# zasilanie.net
KiCad netlist of a schematic drawn in Altium Designer
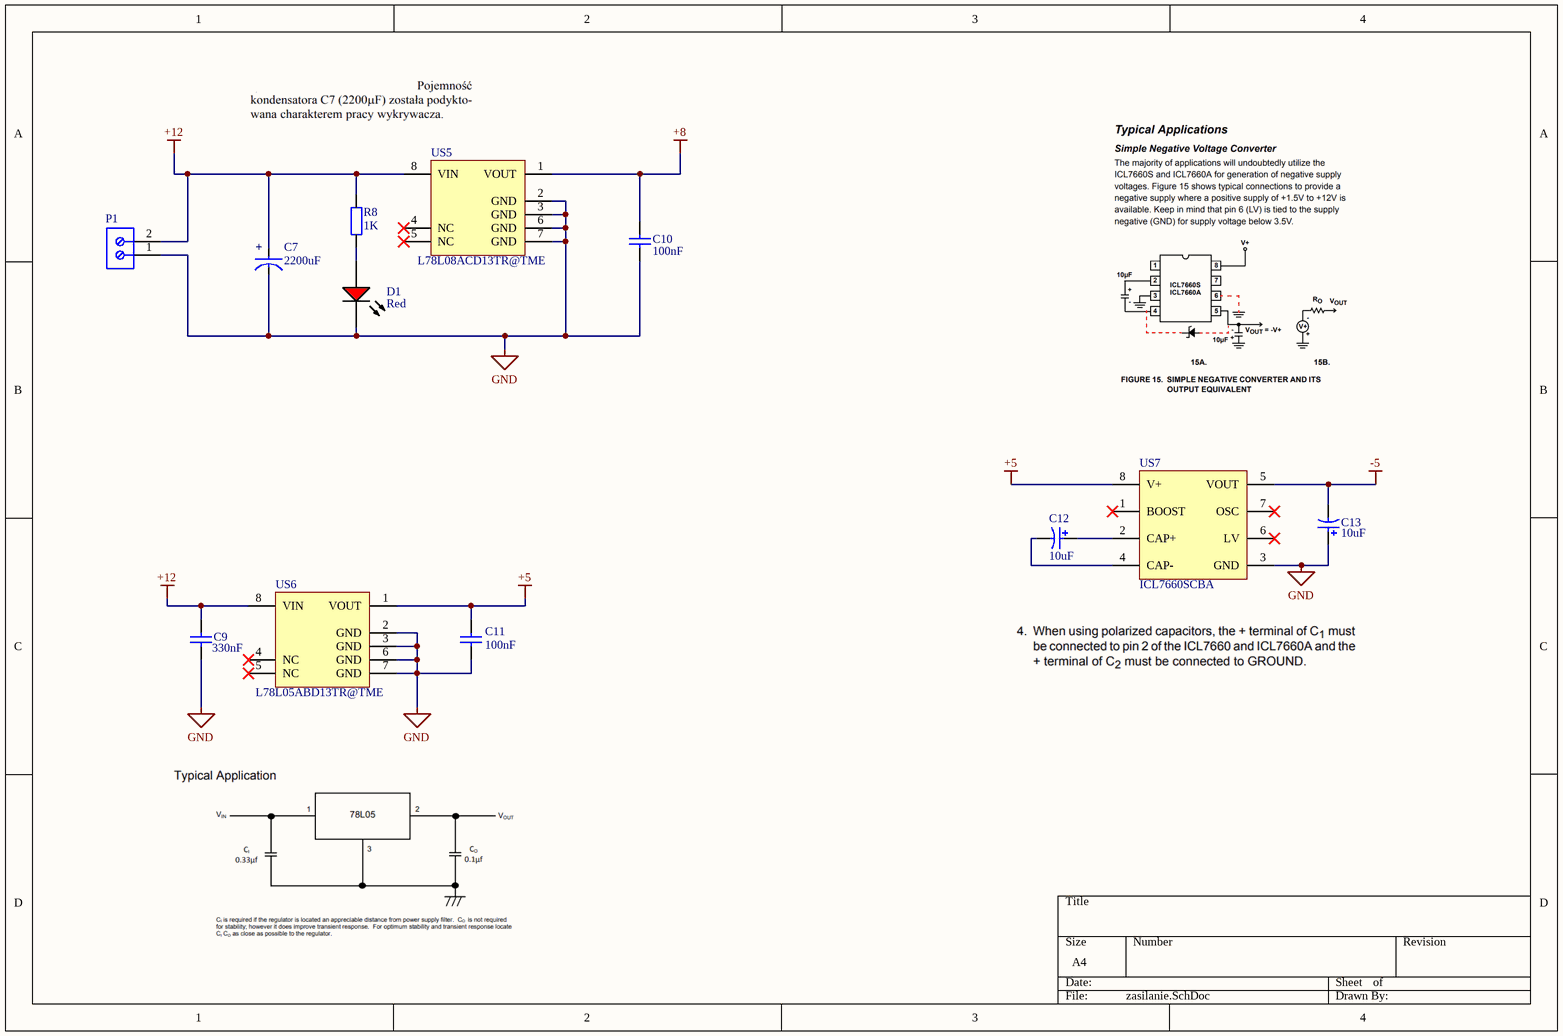
[diagram p0: zasilanie.SchDoc]

(export (version "E")
  (design (tool "Eeschema 10.0.6"))
  (components
    (comp (ref "C7")
      (value "Cap Electrolytic")
      (footprint "Capacitors_MT_Library:18 X 25mm Radial 7.5mm")
      (description "CAPACITOR ALUM 2200UF 20% 35V RADIAL")
      (fields (field (name "CAPACITANCE") "2200uF"))
      (libsource (lib "MT_Library") (part "Cap Electrolytic"))
    )
    (comp (ref "C9")
      (value "330nF")
      (footprint "CAPC1608X90X35ML15T15")
      (fields
        (field (name "PART NUMBER") "0603YD334KAT2A")
        (field (name "MANUFACTURER") "AVX Interconnect / Elco")
      )
      (libsource (lib "Altium Content Vault") (part "CAP"))
    )
    (comp (ref "C10")
      (value "CL10B104KA8NNNC@TME")
      (footprint "0603")
      (description "Capacitor")
      (fields (field (name "CAPACITANCE") "100nF"))
      (libsource (lib "MT_Library") (part "Cap"))
    )
    (comp (ref "C11")
      (value "CL10B104KA8NNNC@TME")
      (footprint "0603")
      (description "Capacitor")
      (fields (field (name "CAPACITANCE") "100nF"))
      (libsource (lib "MT_Library") (part "Cap"))
    )
    (comp (ref "C12")
      (value "EEEFK1H100P")
      (footprint "PNSC-FK-V-D_V")
      (fields (field (name "MANUFACTURER") "Panasonic") (field (name "CAPACITANCE") "10uF"))
      (libsource (lib "Altium Content Vault") (part "CAP-P-2"))
    )
    (comp (ref "C13")
      (value "EEEFK1H100P")
      (footprint "PNSC-FK-V-D_V")
      (fields (field (name "MANUFACTURER") "Panasonic") (field (name "CAPACITANCE") "10uF"))
      (libsource (lib "Altium Content Vault") (part "CAP-P-2"))
    )
    (comp (ref "D1")
      (value "TLMS1000-GS08")
      (footprint "VISH-TLMS1000_V")
      (description "Low Current LED, 40 mW, 1.8 V, -40 to 100 degC, 2-Pin SMD (0603), RoHS, Tape and Reel")
      (fields (field (name "LED COLOUR") "Red") (field (name "MANUFACTURER") "Vishay"))
      (libsource (lib "Altium Content Vault") (part "LED-RED-AK-2"))
    )
    (comp (ref "P1")
      (value "282836-2@TME")
      (footprint "TECO-282836-2_V")
      (description "Female Header, Pitch 5 mm, 1 x 2 Position, Height 10 mm, Tail Length 3.5 mm, Rohs, Bulk")
      (fields (field (name "VOLTAGE") "300V") (field (name "MANUFACTURER") "TE Connectivity"))
      (libsource (lib "Altium Content Vault") (part "CN-1P-F-TB2"))
    )
    (comp (ref "R8")
      (value "1K")
      (footprint "R1206")
      (description "Resistor")
      (fields (field (name "Comment") "1206S4J0102T5E@TME"))
      (libsource (lib "MT_Library") (part "Res"))
    )
    (comp (ref "US5")
      (value "L78L08ACD13TR@TME")
      (footprint "SO8_M")
      (description "Positive Voltage Regulator, 8V, 8-Pin SO, Tape and Reel")
      (libsource (lib "Altium Content Vault") (part "PM-REG-7805-IL8"))
    )
    (comp (ref "US6")
      (value "L78L05ABD13TR@TME")
      (footprint "SO8_N")
      (description "Positive Voltage Regulator, 5V, 8-Pin SO, Tape and Reel")
      (libsource (lib "Altium Content Vault") (part "PM-REG-7805-IL8"))
    )
    (comp (ref "US7")
      (value "ICL7660SCBA")
      (footprint "INTS-SOIC-8_V")
      (fields (field (name "MANUFACTURER") "Intersil"))
      (libsource (lib "Altium Content Vault") (part "INTS-ICL7660S-8"))
    )
  )
  (nets
    (net (code "1") (name "+5") (class "Default")
      (node (ref "C11") (pin "1") (pinfunction "1_1") (pintype "passive"))
      (node (ref "US6") (pin "1") (pinfunction "VOUT_1") (pintype "power_in"))
      (node (ref "US7") (pin "8") (pinfunction "V+_8") (pintype "power_in"))
    )
    (net (code "2") (name "+8") (class "Default")
      (node (ref "C10") (pin "1") (pinfunction "1_1") (pintype "passive"))
      (node (ref "US5") (pin "1") (pinfunction "VOUT_1") (pintype "power_in"))
    )
    (net (code "3") (name "+12") (class "Default")
      (node (ref "C7") (pin "2") (pinfunction "+_2") (pintype "passive"))
      (node (ref "C9") (pin "1") (pinfunction "1_1") (pintype "passive"))
      (node (ref "P1") (pin "2") (pinfunction "-_2") (pintype "power_in"))
      (node (ref "R8") (pin "2") (pinfunction "2_2") (pintype "passive"))
      (node (ref "US5") (pin "8") (pinfunction "VIN_8") (pintype "power_in"))
      (node (ref "US6") (pin "8") (pinfunction "VIN_8") (pintype "power_in"))
    )
    (net (code "4") (name "-5") (class "Default")
      (node (ref "C13") (pin "2") (pinfunction "2_2") (pintype "passive"))
      (node (ref "US7") (pin "5") (pinfunction "VOUT_5") (pintype "power_in"))
    )
    (net (code "5") (name "GND") (class "Default")
      (node (ref "C10") (pin "2") (pinfunction "2_2") (pintype "passive"))
      (node (ref "C11") (pin "2") (pinfunction "2_2") (pintype "passive"))
      (node (ref "C13") (pin "1") (pinfunction "1_1") (pintype "passive"))
      (node (ref "C7") (pin "1") (pinfunction "-_1") (pintype "passive"))
      (node (ref "C9") (pin "2") (pinfunction "2_2") (pintype "passive"))
      (node (ref "D1") (pin "2") (pinfunction "K_2") (pintype "passive"))
      (node (ref "P1") (pin "1") (pinfunction "+_1") (pintype "power_in"))
      (node (ref "US5") (pin "2") (pinfunction "GND_2") (pintype "power_in"))
      (node (ref "US5") (pin "3") (pinfunction "GND_3") (pintype "power_in"))
      (node (ref "US5") (pin "6") (pinfunction "GND_6") (pintype "power_in"))
      (node (ref "US5") (pin "7") (pinfunction "GND_7") (pintype "power_in"))
      (node (ref "US6") (pin "2") (pinfunction "GND_2") (pintype "power_in"))
      (node (ref "US6") (pin "3") (pinfunction "GND_3") (pintype "power_in"))
      (node (ref "US6") (pin "6") (pinfunction "GND_6") (pintype "power_in"))
      (node (ref "US6") (pin "7") (pinfunction "GND_7") (pintype "power_in"))
      (node (ref "US7") (pin "3") (pinfunction "GND_3") (pintype "power_in"))
    )
    (net (code "6") (name "Net-(D1-A)") (class "Default")
      (node (ref "D1") (pin "1") (pinfunction "A_1") (pintype "passive"))
      (node (ref "R8") (pin "1") (pinfunction "1_1") (pintype "passive"))
    )
    (net (code "7") (name "Net-(US7-CAP+)") (class "Default")
      (node (ref "C12") (pin "1") (pinfunction "1_1") (pintype "passive"))
      (node (ref "US7") (pin "2") (pinfunction "CAP+_2") (pintype "passive"))
    )
    (net (code "8") (name "Net-(US7-CAP-)") (class "Default")
      (node (ref "C12") (pin "2") (pinfunction "2_2") (pintype "passive"))
      (node (ref "US7") (pin "4") (pinfunction "CAP-_4") (pintype "passive"))
    )
    (net (code "9") (name "unconnected-(US5-NC-Pad4)") (class "Default")
      (node (ref "US5") (pin "4") (pinfunction "NC_4") (pintype "passive+no_connect"))
    )
    (net (code "10") (name "unconnected-(US5-NC-Pad5)") (class "Default")
      (node (ref "US5") (pin "5") (pinfunction "NC_5") (pintype "passive+no_connect"))
    )
    (net (code "11") (name "unconnected-(US6-NC-Pad4)") (class "Default")
      (node (ref "US6") (pin "4") (pinfunction "NC_4") (pintype "passive+no_connect"))
    )
    (net (code "12") (name "unconnected-(US6-NC-Pad5)") (class "Default")
      (node (ref "US6") (pin "5") (pinfunction "NC_5") (pintype "passive+no_connect"))
    )
    (net (code "13") (name "unconnected-(US7-BOOST-Pad1)") (class "Default")
      (node (ref "US7") (pin "1") (pinfunction "BOOST_1") (pintype "passive+no_connect"))
    )
    (net (code "14") (name "unconnected-(US7-LV-Pad6)") (class "Default")
      (node (ref "US7") (pin "6") (pinfunction "LV_6") (pintype "power_in+no_connect"))
    )
    (net (code "15") (name "unconnected-(US7-OSC-Pad7)") (class "Default")
      (node (ref "US7") (pin "7") (pinfunction "OSC_7") (pintype "passive+no_connect"))
    )
  )
)
